# Thermistor.net
KiCad netlist of a schematic drawn in Altium Designer
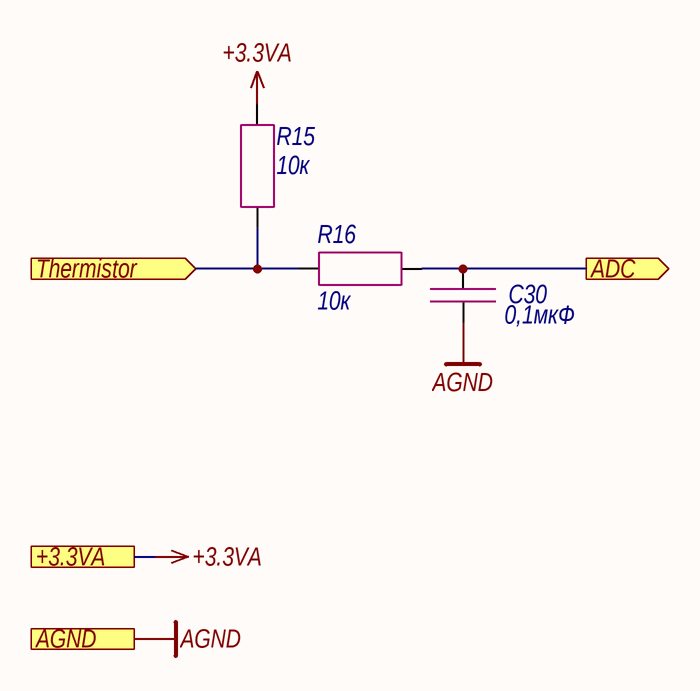
[diagram p0: Thermistor.SchDoc]

(export (version "E")
  (design (tool "Eeschema 10.0.6"))
  (components
    (comp (ref "C30")
      (value "0,1мкФ")
      (footprint "Pcb_library:CAP_0603")
      (fields (field (name "MANUFACTURER") "Murata"))
      (libsource (lib "Schem_library") (part "Capacitor"))
    )
    (comp (ref "R15")
      (value "10к")
      (footprint "Pcb_library:RES_0603")
      (fields (field (name "MANUFACTURER") "Yageo"))
      (libsource (lib "Schem_library") (part "Resistor"))
    )
    (comp (ref "R16")
      (value "10к")
      (footprint "Pcb_library:RES_0603")
      (fields (field (name "MANUFACTURER") "Yageo"))
      (libsource (lib "Schem_library") (part "Resistor"))
    )
  )
  (nets
    (net (code "1") (name "+3.3VA") (class "Default")
      (node (ref "R15") (pin "1") (pinfunction "1_1") (pintype "passive"))
    )
    (net (code "2") (name "/ADC") (class "Default")
      (node (ref "C30") (pin "1") (pinfunction "1_1") (pintype "passive"))
      (node (ref "R16") (pin "2") (pinfunction "2_2") (pintype "passive"))
    )
    (net (code "3") (name "/Thermistor") (class "Default")
      (node (ref "R15") (pin "2") (pinfunction "2_2") (pintype "passive"))
      (node (ref "R16") (pin "1") (pinfunction "1_1") (pintype "passive"))
    )
    (net (code "4") (name "AGND") (class "Default")
      (node (ref "C30") (pin "2") (pinfunction "2_2") (pintype "passive"))
    )
  )
)
